# Signal_In.net
KiCad netlist of a schematic drawn in Altium Designer
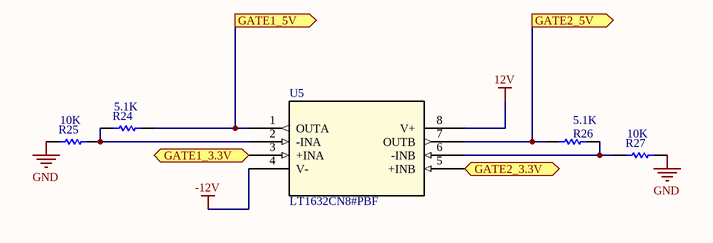
[diagram p0: Signal_In.SchDoc]

(export (version "E")
  (design (tool "Eeschema 10.0.6"))
  (components
    (comp (ref "R24")
      (value "5.1K")
      (footprint "AXIAL-0.3")
      (description "Resistor")
      (fields (field (name "Comment") "Res1") (field (name "PUBLISHER") "Altium Limited"))
      (libsource (lib "Miscellaneous Devices") (part "Res1"))
    )
    (comp (ref "R25")
      (value "10K")
      (footprint "AXIAL-0.3")
      (description "Resistor")
      (fields (field (name "Comment") "Res1") (field (name "PUBLISHER") "Altium Limited"))
      (libsource (lib "Miscellaneous Devices") (part "Res1"))
    )
    (comp (ref "R26")
      (value "5.1K")
      (footprint "AXIAL-0.3")
      (description "Resistor")
      (fields (field (name "Comment") "Res1") (field (name "PUBLISHER") "Altium Limited"))
      (libsource (lib "Miscellaneous Devices") (part "Res1"))
    )
    (comp (ref "R27")
      (value "10K")
      (footprint "AXIAL-0.3")
      (description "Resistor")
      (fields (field (name "Comment") "Res1") (field (name "PUBLISHER") "Altium Limited"))
      (libsource (lib "Miscellaneous Devices") (part "Res1"))
    )
    (comp (ref "U5")
      (value "LT1632CN8#PBF")
      (footprint "PDIP-8_N")
      (description "Imported")
      (fields
        (field (name "DIGIKEYPARTNUMBER") "LT1632CN8-ND")
        (field (name "COPYRIGHT") "Copyright (C) 2015 Accelerated Designs. All rights reserved")
      )
      (libsource (lib "lt1632") (part "LT1632CN8#PBF"))
    )
  )
  (nets
    (net (code "1") (name "-12V") (class "Default")
      (node (ref "U5") (pin "4") (pinfunction "V-_4") (pintype "power_in"))
    )
    (net (code "2") (name "/GATE1_3.3V") (class "Default")
      (node (ref "U5") (pin "3") (pinfunction "+INA_3") (pintype "input"))
    )
    (net (code "3") (name "/GATE1_5V") (class "Default")
      (node (ref "R24") (pin "2") (pinfunction "2_2") (pintype "passive"))
      (node (ref "U5") (pin "1") (pinfunction "OUTA_1") (pintype "output"))
    )
    (net (code "4") (name "/GATE2_3.3V") (class "Default")
      (node (ref "U5") (pin "5") (pinfunction "+INB_5") (pintype "input"))
    )
    (net (code "5") (name "/GATE2_5V") (class "Default")
      (node (ref "R26") (pin "1") (pinfunction "1_1") (pintype "passive"))
      (node (ref "U5") (pin "7") (pinfunction "OUTB_7") (pintype "output"))
    )
    (net (code "6") (name "12V") (class "Default")
      (node (ref "U5") (pin "8") (pinfunction "V+_8") (pintype "power_in"))
    )
    (net (code "7") (name "GND") (class "Default")
      (node (ref "R25") (pin "1") (pinfunction "1_1") (pintype "passive"))
      (node (ref "R27") (pin "2") (pinfunction "2_2") (pintype "passive"))
    )
    (net (code "8") (name "Net-(U5--INA)") (class "Default")
      (node (ref "R24") (pin "1") (pinfunction "1_1") (pintype "passive"))
      (node (ref "R25") (pin "2") (pinfunction "2_2") (pintype "passive"))
      (node (ref "U5") (pin "2") (pinfunction "-INA_2") (pintype "input"))
    )
    (net (code "9") (name "Net-(U5--INB)") (class "Default")
      (node (ref "R26") (pin "2") (pinfunction "2_2") (pintype "passive"))
      (node (ref "R27") (pin "1") (pinfunction "1_1") (pintype "passive"))
      (node (ref "U5") (pin "6") (pinfunction "-INB_6") (pintype "input"))
    )
  )
)
